# Sheet1.net
KiCad netlist of a schematic drawn in Altium Designer
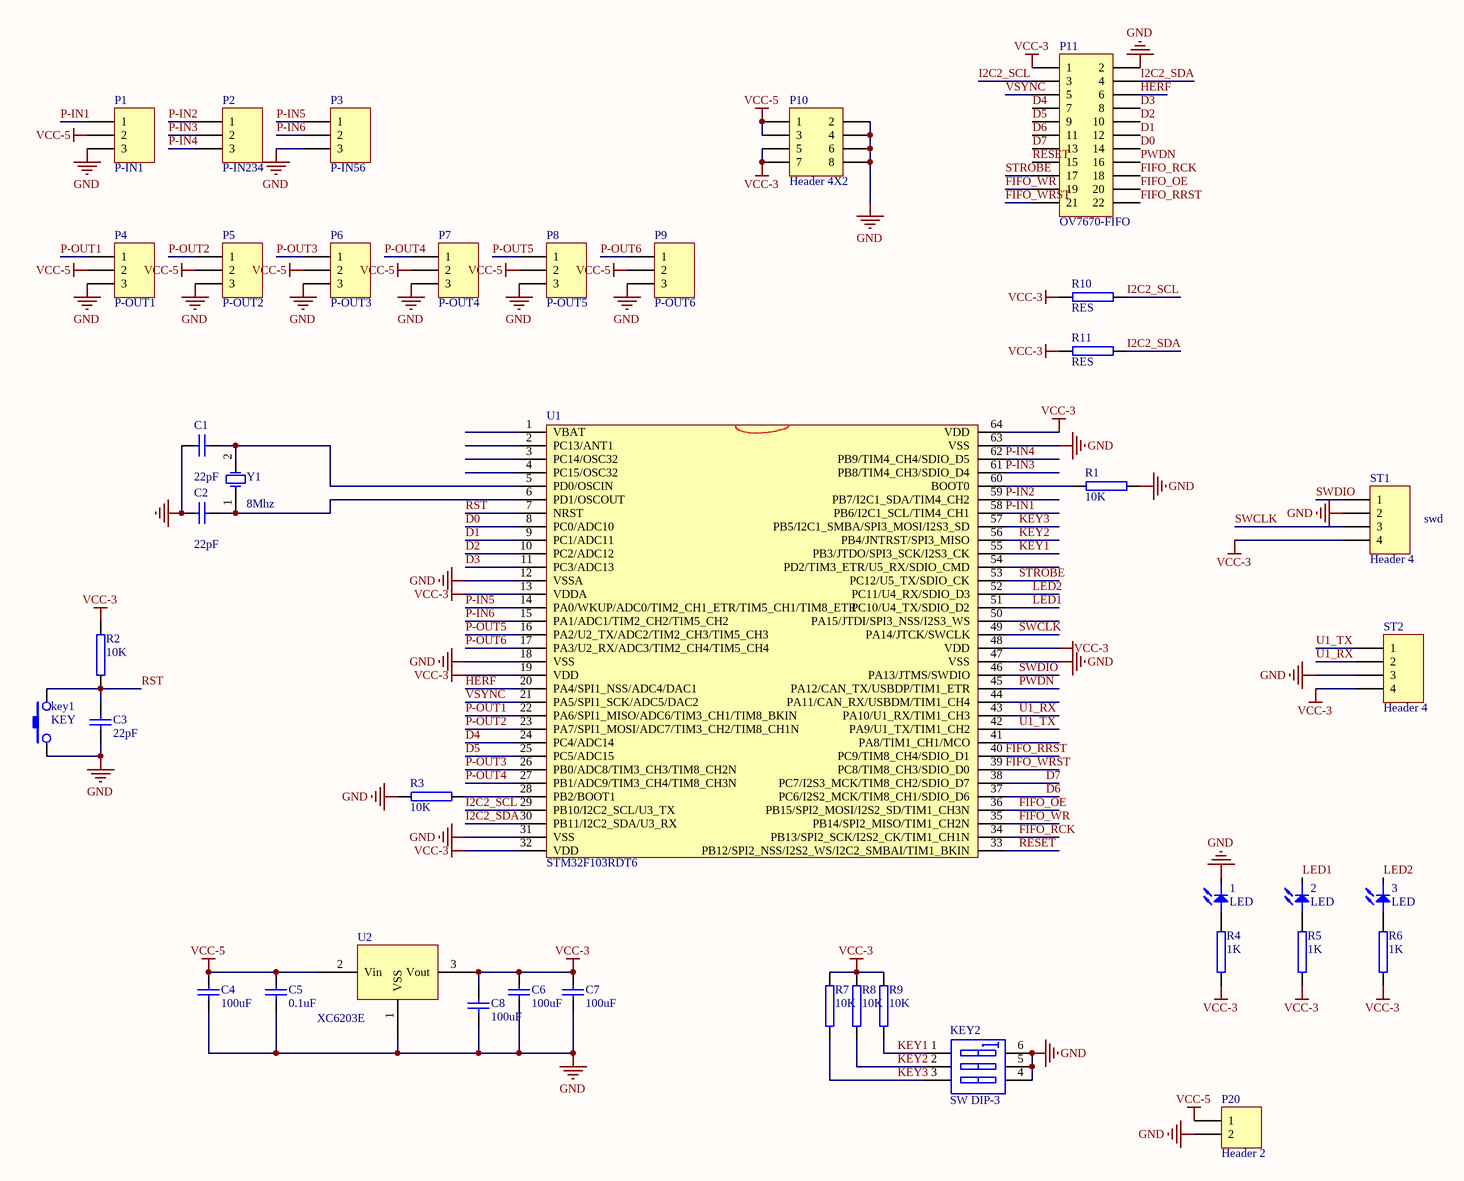
[diagram p0: Sheet1.SchDoc]

(export (version "E")
  (design (tool "Eeschema 10.0.6"))
  (components
    (comp (ref "1") (value "LED") (footprint "0603c") (libsource (lib "常用元件库") (part "LED")))
    (comp (ref "2") (value "LED") (footprint "0603c") (libsource (lib "常用元件库") (part "LED")))
    (comp (ref "3") (value "LED") (footprint "0603c") (libsource (lib "常用元件库") (part "LED")))
    (comp (ref "C1")
      (value "22pF")
      (footprint "0603c")
      (fields (field (name "Comment") "cap"))
      (libsource (lib "bai") (part "cap"))
    )
    (comp (ref "C2")
      (value "22pF")
      (footprint "0603c")
      (fields (field (name "Comment") "cap"))
      (libsource (lib "bai") (part "cap"))
    )
    (comp (ref "C3")
      (value "22pF")
      (footprint "0603c")
      (fields (field (name "Comment") "cap"))
      (libsource (lib "bai") (part "cap"))
    )
    (comp (ref "C4")
      (value "100uF")
      (footprint "0603c")
      (fields (field (name "Comment") "cap"))
      (libsource (lib "bai") (part "cap"))
    )
    (comp (ref "C5")
      (value "0.1uF")
      (footprint "0603c")
      (fields (field (name "Comment") "cap"))
      (libsource (lib "bai") (part "cap"))
    )
    (comp (ref "C6")
      (value "100uF")
      (footprint "0603c")
      (fields (field (name "Comment") "cap"))
      (libsource (lib "bai") (part "cap"))
    )
    (comp (ref "C7")
      (value "100uF")
      (footprint "0603c")
      (fields (field (name "Comment") "cap"))
      (libsource (lib "bai") (part "cap"))
    )
    (comp (ref "C8")
      (value "100uF")
      (footprint "0603c")
      (fields (field (name "Comment") "cap"))
      (libsource (lib "bai") (part "cap"))
    )
    (comp (ref "key1") (value "KEY") (footprint "7243") (libsource (lib "常用元件库") (part "KEY")))
    (comp (ref "KEY2")
      (value "SW DIP-3")
      (footprint "DIP6")
      (description "DIP Switch")
      (libsource (lib "开关") (part "SW DIP-3"))
    )
    (comp (ref "P1")
      (value "P-IN1")
      (footprint "HDR1X3")
      (description "Header, 3-Pin")
      (fields (field (name "PUBLISHER") "Altium Limited"))
      (libsource (lib "Miscellaneous Connectors") (part "MHDR1X3"))
    )
    (comp (ref "P2")
      (value "P-IN234")
      (footprint "HDR1X3")
      (description "Header, 3-Pin")
      (fields (field (name "PUBLISHER") "Altium Limited"))
      (libsource (lib "Miscellaneous Connectors") (part "MHDR1X3"))
    )
    (comp (ref "P3")
      (value "P-IN56")
      (footprint "HDR1X3")
      (description "Header, 3-Pin")
      (fields (field (name "PUBLISHER") "Altium Limited"))
      (libsource (lib "Miscellaneous Connectors") (part "MHDR1X3"))
    )
    (comp (ref "P4")
      (value "P-OUT1")
      (footprint "HDR1X3")
      (description "Header, 3-Pin")
      (fields (field (name "PUBLISHER") "Altium Limited"))
      (libsource (lib "Miscellaneous Connectors") (part "MHDR1X3"))
    )
    (comp (ref "P5")
      (value "P-OUT2")
      (footprint "HDR1X3")
      (description "Header, 3-Pin")
      (fields (field (name "PUBLISHER") "Altium Limited"))
      (libsource (lib "Miscellaneous Connectors") (part "MHDR1X3"))
    )
    (comp (ref "P6")
      (value "P-OUT3")
      (footprint "HDR1X3")
      (description "Header, 3-Pin")
      (fields (field (name "PUBLISHER") "Altium Limited"))
      (libsource (lib "Miscellaneous Connectors") (part "MHDR1X3"))
    )
    (comp (ref "P7")
      (value "P-OUT4")
      (footprint "HDR1X3")
      (description "Header, 3-Pin")
      (fields (field (name "PUBLISHER") "Altium Limited"))
      (libsource (lib "Miscellaneous Connectors") (part "MHDR1X3"))
    )
    (comp (ref "P8")
      (value "P-OUT5")
      (footprint "HDR1X3")
      (description "Header, 3-Pin")
      (fields (field (name "PUBLISHER") "Altium Limited"))
      (libsource (lib "Miscellaneous Connectors") (part "MHDR1X3"))
    )
    (comp (ref "P9")
      (value "P-OUT6")
      (footprint "HDR1X3")
      (description "Header, 3-Pin")
      (fields (field (name "PUBLISHER") "Altium Limited"))
      (libsource (lib "Miscellaneous Connectors") (part "MHDR1X3"))
    )
    (comp (ref "P10")
      (value "Header 4X2")
      (footprint "HDR2X4")
      (description "Header, 4-Pin, Dual row")
      (fields (field (name "PUBLISHER") "Altium Limited"))
      (libsource (lib "Miscellaneous Connectors") (part "Header 4X2"))
    )
    (comp (ref "P11")
      (value "OV7670-FIFO")
      (footprint "HDR2X11")
      (description "Header, 11-Pin, Dual row")
      (fields (field (name "PUBLISHER") "Altium Limited"))
      (libsource (lib "Miscellaneous Connectors") (part "Header 11X2"))
    )
    (comp (ref "P20")
      (value "Header 2")
      (footprint "HDR1X2")
      (description "Header, 2-Pin")
      (fields (field (name "PUBLISHER") "Altium Limited"))
      (libsource (lib "Miscellaneous Connectors") (part "Header 2"))
    )
    (comp (ref "R1") (value "10K") (footprint "0603c") (libsource (lib "常用元件库") (part "RES")))
    (comp (ref "R2") (value "10K") (footprint "0603c") (libsource (lib "常用元件库") (part "RES")))
    (comp (ref "R3") (value "10K") (footprint "0603c") (libsource (lib "常用元件库") (part "RES")))
    (comp (ref "R4") (value "1K") (footprint "0603c") (libsource (lib "常用元件库") (part "RES")))
    (comp (ref "R5") (value "1K") (footprint "0603c") (libsource (lib "常用元件库") (part "RES")))
    (comp (ref "R6") (value "1K") (footprint "0603c") (libsource (lib "常用元件库") (part "RES")))
    (comp (ref "R7") (value "10K") (footprint "0603c") (libsource (lib "常用元件库") (part "RES")))
    (comp (ref "R8") (value "10K") (footprint "0603c") (libsource (lib "常用元件库") (part "RES")))
    (comp (ref "R9") (value "10K") (footprint "0603c") (libsource (lib "常用元件库") (part "RES")))
    (comp (ref "R10") (value "RES") (footprint "0603c") (libsource (lib "常用元件库") (part "RES")))
    (comp (ref "R11") (value "RES") (footprint "0603c") (libsource (lib "常用元件库") (part "RES")))
    (comp (ref "ST1")
      (value "Header 4")
      (footprint "HDR1X4")
      (description "Header, 4-Pin")
      (fields (field (name "PUBLISHER") "Altium Limited"))
      (libsource (lib "Miscellaneous Connectors") (part "Header 4"))
    )
    (comp (ref "ST2")
      (value "Header 4")
      (footprint "HDR1X4")
      (description "Header, 4-Pin")
      (fields (field (name "PUBLISHER") "Altium Limited"))
      (libsource (lib "Miscellaneous Connectors") (part "Header 4"))
    )
    (comp (ref "U1")
      (value "STM32F103RDT6")
      (footprint "stm32:LQFP64")
      (libsource (lib "stm32") (part "STM32F103RDT6"))
    )
    (comp (ref "U2") (value "XC6203E") (footprint "SOT-89") (libsource (lib "文哥做的") (part "XC6203")))
    (comp (ref "Y1")
      (value "5032xtal")
      (footprint "XTAL")
      (fields (field (name "ALTIUM_UNNAMED_1") "8Mhz"))
      (libsource (lib "bai") (part "5032xtal"))
    )
  )
  (nets
    (net (code "1") (name "/D0") (class "Default")
      (node (ref "P11") (pin "14") (pinfunction "14_14") (pintype "passive"))
      (node (ref "U1") (pin "8") (pinfunction "PC0/ADC10_8") (pintype "passive"))
    )
    (net (code "2") (name "/D1") (class "Default")
      (node (ref "P11") (pin "12") (pinfunction "12_12") (pintype "passive"))
      (node (ref "U1") (pin "9") (pinfunction "PC1/ADC11_9") (pintype "passive"))
    )
    (net (code "3") (name "/D2") (class "Default")
      (node (ref "P11") (pin "10") (pinfunction "10_10") (pintype "passive"))
      (node (ref "U1") (pin "10") (pinfunction "PC2/ADC12_10") (pintype "passive"))
    )
    (net (code "4") (name "/D3") (class "Default")
      (node (ref "P11") (pin "8") (pinfunction "8_8") (pintype "passive"))
      (node (ref "U1") (pin "11") (pinfunction "PC3/ADC13_11") (pintype "passive"))
    )
    (net (code "5") (name "/D4") (class "Default")
      (node (ref "P11") (pin "7") (pinfunction "7_7") (pintype "passive"))
      (node (ref "U1") (pin "24") (pinfunction "PC4/ADC14_24") (pintype "passive"))
    )
    (net (code "6") (name "/D5") (class "Default")
      (node (ref "P11") (pin "9") (pinfunction "9_9") (pintype "passive"))
      (node (ref "U1") (pin "25") (pinfunction "PC5/ADC15_25") (pintype "passive"))
    )
    (net (code "7") (name "/D6") (class "Default")
      (node (ref "P11") (pin "11") (pinfunction "11_11") (pintype "passive"))
      (node (ref "U1") (pin "37") (pinfunction "PC6/I2S2_MCK/TIM8_CH1/SDIO_D6_37") (pintype "passive"))
    )
    (net (code "8") (name "/D7") (class "Default")
      (node (ref "P11") (pin "13") (pinfunction "13_13") (pintype "passive"))
      (node (ref "U1") (pin "38") (pinfunction "PC7/I2S3_MCK/TIM8_CH2/SDIO_D7_38") (pintype "passive"))
    )
    (net (code "9") (name "/FIFO_OE") (class "Default")
      (node (ref "P11") (pin "20") (pinfunction "20_20") (pintype "passive"))
      (node (ref "U1") (pin "36") (pinfunction "PB15/SPI2_MOSI/I2S2_SD/TIM1_CH3N_36") (pintype "passive"))
    )
    (net (code "10") (name "/FIFO_RCK") (class "Default")
      (node (ref "P11") (pin "18") (pinfunction "18_18") (pintype "passive"))
      (node (ref "U1") (pin "34") (pinfunction "PB13/SPI2_SCK/I2S2_CK/TIM1_CH1N_34") (pintype "passive"))
    )
    (net (code "11") (name "/FIFO_RRST") (class "Default")
      (node (ref "P11") (pin "22") (pinfunction "22_22") (pintype "passive"))
      (node (ref "U1") (pin "40") (pinfunction "PC9/TIM8_CH4/SDIO_D1_40") (pintype "passive"))
    )
    (net (code "12") (name "/FIFO_WR") (class "Default")
      (node (ref "P11") (pin "19") (pinfunction "19_19") (pintype "passive"))
      (node (ref "U1") (pin "35") (pinfunction "PB14/SPI2_MISO/TIM1_CH2N_35") (pintype "passive"))
    )
    (net (code "13") (name "/FIFO_WRST") (class "Default")
      (node (ref "P11") (pin "21") (pinfunction "21_21") (pintype "passive"))
      (node (ref "U1") (pin "39") (pinfunction "PC8/TIM8_CH3/SDIO_D0_39") (pintype "passive"))
    )
    (net (code "14") (name "/HERF") (class "Default")
      (node (ref "P11") (pin "6") (pinfunction "6_6") (pintype "passive"))
      (node (ref "U1") (pin "20") (pinfunction "PA4/SPI1_NSS/ADC4/DAC1_20") (pintype "passive"))
    )
    (net (code "15") (name "/I2C2_SCL") (class "Default")
      (node (ref "P11") (pin "3") (pinfunction "3_3") (pintype "passive"))
      (node (ref "R10") (pin "2") (pinfunction "2_2") (pintype "passive"))
      (node (ref "U1") (pin "29") (pinfunction "PB10/I2C2_SCL/U3_TX_29") (pintype "passive"))
    )
    (net (code "16") (name "/I2C2_SDA") (class "Default")
      (node (ref "P11") (pin "4") (pinfunction "4_4") (pintype "passive"))
      (node (ref "R11") (pin "2") (pinfunction "2_2") (pintype "passive"))
      (node (ref "U1") (pin "30") (pinfunction "PB11/I2C2_SDA/U3_RX_30") (pintype "passive"))
    )
    (net (code "17") (name "/KEY1") (class "Default")
      (node (ref "KEY2") (pin "1") (pinfunction "A1_1") (pintype "passive"))
      (node (ref "R9") (pin "1") (pinfunction "1_1") (pintype "passive"))
      (node (ref "U1") (pin "55") (pinfunction "PB3/JTDO/SPI3_SCK/I2S3_CK_55") (pintype "passive"))
    )
    (net (code "18") (name "/KEY2") (class "Default")
      (node (ref "KEY2") (pin "2") (pinfunction "A2_2") (pintype "passive"))
      (node (ref "R8") (pin "1") (pinfunction "1_1") (pintype "passive"))
      (node (ref "U1") (pin "56") (pinfunction "PB4/JNTRST/SPI3_MISO_56") (pintype "passive"))
    )
    (net (code "19") (name "/KEY3") (class "Default")
      (node (ref "KEY2") (pin "3") (pinfunction "A3_3") (pintype "passive"))
      (node (ref "R7") (pin "1") (pinfunction "1_1") (pintype "passive"))
      (node (ref "U1") (pin "57") (pinfunction "PB5/I2C1_SMBA/SPI3_MOSI/I2S3_SD_57") (pintype "passive"))
    )
    (net (code "20") (name "/LED1") (class "Default")
      (node (ref "2") (pin "K") (pintype "passive"))
      (node (ref "U1") (pin "51") (pinfunction "PC10/U4_TX/SDIO_D2_51") (pintype "passive"))
    )
    (net (code "21") (name "/LED2") (class "Default")
      (node (ref "3") (pin "K") (pintype "passive"))
      (node (ref "U1") (pin "52") (pinfunction "PC11/U4_RX/SDIO_D3_52") (pintype "passive"))
    )
    (net (code "22") (name "/P-IN1") (class "Default")
      (node (ref "P1") (pin "1") (pinfunction "1_1") (pintype "passive"))
      (node (ref "U1") (pin "58") (pinfunction "PB6/I2C1_SCL/TIM4_CH1_58") (pintype "passive"))
    )
    (net (code "23") (name "/P-IN2") (class "Default")
      (node (ref "P2") (pin "1") (pinfunction "1_1") (pintype "passive"))
      (node (ref "U1") (pin "59") (pinfunction "PB7/I2C1_SDA/TIM4_CH2_59") (pintype "passive"))
    )
    (net (code "24") (name "/P-IN3") (class "Default")
      (node (ref "P2") (pin "2") (pinfunction "2_2") (pintype "passive"))
      (node (ref "U1") (pin "61") (pinfunction "PB8/TIM4_CH3/SDIO_D4_61") (pintype "passive"))
    )
    (net (code "25") (name "/P-IN4") (class "Default")
      (node (ref "P2") (pin "3") (pinfunction "3_3") (pintype "passive"))
      (node (ref "U1") (pin "62") (pinfunction "PB9/TIM4_CH4/SDIO_D5_62") (pintype "passive"))
    )
    (net (code "26") (name "/P-IN5") (class "Default")
      (node (ref "P3") (pin "1") (pinfunction "1_1") (pintype "passive"))
      (node (ref "U1") (pin "14") (pinfunction "PA0/WKUP/ADC0/TIM2_CH1_ETR/TIM5_CH1/TIM8_ETR_14") (pintype "passive"))
    )
    (net (code "27") (name "/P-IN6") (class "Default")
      (node (ref "P3") (pin "2") (pinfunction "2_2") (pintype "passive"))
      (node (ref "U1") (pin "15") (pinfunction "PA1/ADC1/TIM2_CH2/TIM5_CH2_15") (pintype "passive"))
    )
    (net (code "28") (name "/P-OUT1") (class "Default")
      (node (ref "P4") (pin "1") (pinfunction "1_1") (pintype "passive"))
      (node (ref "U1") (pin "22") (pinfunction "PA6/SPI1_MISO/ADC6/TIM3_CH1/TIM8_BKIN_22") (pintype "passive"))
    )
    (net (code "29") (name "/P-OUT2") (class "Default")
      (node (ref "P5") (pin "1") (pinfunction "1_1") (pintype "passive"))
      (node (ref "U1") (pin "23") (pinfunction "PA7/SPI1_MOSI/ADC7/TIM3_CH2/TIM8_CH1N_23") (pintype "passive"))
    )
    (net (code "30") (name "/P-OUT3") (class "Default")
      (node (ref "P6") (pin "1") (pinfunction "1_1") (pintype "passive"))
      (node (ref "U1") (pin "26") (pinfunction "PB0/ADC8/TIM3_CH3/TIM8_CH2N_26") (pintype "passive"))
    )
    (net (code "31") (name "/P-OUT4") (class "Default")
      (node (ref "P7") (pin "1") (pinfunction "1_1") (pintype "passive"))
      (node (ref "U1") (pin "27") (pinfunction "PB1/ADC9/TIM3_CH4/TIM8_CH3N_27") (pintype "passive"))
    )
    (net (code "32") (name "/P-OUT5") (class "Default")
      (node (ref "P8") (pin "1") (pinfunction "1_1") (pintype "passive"))
      (node (ref "U1") (pin "16") (pinfunction "PA2/U2_TX/ADC2/TIM2_CH3/TIM5_CH3_16") (pintype "passive"))
    )
    (net (code "33") (name "/P-OUT6") (class "Default")
      (node (ref "P9") (pin "1") (pinfunction "1_1") (pintype "passive"))
      (node (ref "U1") (pin "17") (pinfunction "PA3/U2_RX/ADC3/TIM2_CH4/TIM5_CH4_17") (pintype "passive"))
    )
    (net (code "34") (name "/PWDN") (class "Default")
      (node (ref "P11") (pin "16") (pinfunction "16_16") (pintype "passive"))
      (node (ref "U1") (pin "45") (pinfunction "PA12/CAN_TX/USBDP/TIM1_ETR_45") (pintype "passive"))
    )
    (net (code "35") (name "/RESET") (class "Default")
      (node (ref "P11") (pin "15") (pinfunction "15_15") (pintype "passive"))
      (node (ref "U1") (pin "33") (pinfunction "PB12/SPI2_NSS/I2S2_WS/I2C2_SMBAI/TIM1_BKIN_33") (pintype "passive"))
    )
    (net (code "36") (name "/RST") (class "Default")
      (node (ref "C3") (pin "2") (pinfunction "2_2") (pintype "passive"))
      (node (ref "R2") (pin "1") (pinfunction "1_1") (pintype "passive"))
      (node (ref "U1") (pin "7") (pinfunction "NRST_7") (pintype "passive"))
      (node (ref "key1") (pin "2") (pinfunction "2_2") (pintype "passive"))
    )
    (net (code "37") (name "/STROBE") (class "Default")
      (node (ref "P11") (pin "17") (pinfunction "17_17") (pintype "passive"))
      (node (ref "U1") (pin "53") (pinfunction "PC12/U5_TX/SDIO_CK_53") (pintype "passive"))
    )
    (net (code "38") (name "/SWCLK") (class "Default")
      (node (ref "ST1") (pin "3") (pinfunction "3_3") (pintype "passive"))
      (node (ref "U1") (pin "49") (pinfunction "PA14/JTCK/SWCLK_49") (pintype "passive"))
    )
    (net (code "39") (name "/SWDIO") (class "Default")
      (node (ref "ST1") (pin "1") (pinfunction "1_1") (pintype "passive"))
      (node (ref "U1") (pin "46") (pinfunction "PA13/JTMS/SWDIO_46") (pintype "passive"))
    )
    (net (code "40") (name "/U1_RX") (class "Default")
      (node (ref "ST2") (pin "2") (pinfunction "2_2") (pintype "passive"))
      (node (ref "U1") (pin "43") (pinfunction "PA10/U1_RX/TIM1_CH3_43") (pintype "passive"))
    )
    (net (code "41") (name "/U1_TX") (class "Default")
      (node (ref "ST2") (pin "1") (pinfunction "1_1") (pintype "passive"))
      (node (ref "U1") (pin "42") (pinfunction "PA9/U1_TX/TIM1_CH2_42") (pintype "passive"))
    )
    (net (code "42") (name "/VSYNC") (class "Default")
      (node (ref "P11") (pin "5") (pinfunction "5_5") (pintype "passive"))
      (node (ref "U1") (pin "21") (pinfunction "PA5/SPI1_SCK/ADC5/DAC2_21") (pintype "passive"))
    )
    (net (code "43") (name "GND") (class "Default")
      (node (ref "1") (pin "K") (pintype "passive"))
      (node (ref "C1") (pin "1") (pinfunction "1_1") (pintype "passive"))
      (node (ref "C2") (pin "1") (pinfunction "1_1") (pintype "passive"))
      (node (ref "C3") (pin "1") (pinfunction "1_1") (pintype "passive"))
      (node (ref "C4") (pin "1") (pinfunction "1_1") (pintype "passive"))
      (node (ref "C5") (pin "1") (pinfunction "1_1") (pintype "passive"))
      (node (ref "C6") (pin "1") (pinfunction "1_1") (pintype "passive"))
      (node (ref "C7") (pin "1") (pinfunction "1_1") (pintype "passive"))
      (node (ref "C8") (pin "1") (pinfunction "1_1") (pintype "passive"))
      (node (ref "KEY2") (pin "4") (pinfunction "B3_4") (pintype "passive"))
      (node (ref "KEY2") (pin "5") (pinfunction "B2_5") (pintype "passive"))
      (node (ref "KEY2") (pin "6") (pinfunction "B1_6") (pintype "passive"))
      (node (ref "P1") (pin "3") (pinfunction "3_3") (pintype "passive"))
      (node (ref "P10") (pin "2") (pinfunction "2_2") (pintype "passive"))
      (node (ref "P10") (pin "4") (pinfunction "4_4") (pintype "passive"))
      (node (ref "P10") (pin "6") (pinfunction "6_6") (pintype "passive"))
      (node (ref "P10") (pin "8") (pinfunction "8_8") (pintype "passive"))
      (node (ref "P11") (pin "2") (pinfunction "2_2") (pintype "passive"))
      (node (ref "P20") (pin "2") (pinfunction "2_2") (pintype "passive"))
      (node (ref "P3") (pin "3") (pinfunction "3_3") (pintype "passive"))
      (node (ref "P4") (pin "3") (pinfunction "3_3") (pintype "passive"))
      (node (ref "P5") (pin "3") (pinfunction "3_3") (pintype "passive"))
      (node (ref "P6") (pin "3") (pinfunction "3_3") (pintype "passive"))
      (node (ref "P7") (pin "3") (pinfunction "3_3") (pintype "passive"))
      (node (ref "P8") (pin "3") (pinfunction "3_3") (pintype "passive"))
      (node (ref "P9") (pin "3") (pinfunction "3_3") (pintype "passive"))
      (node (ref "R1") (pin "2") (pinfunction "2_2") (pintype "passive"))
      (node (ref "R3") (pin "2") (pinfunction "2_2") (pintype "passive"))
      (node (ref "ST1") (pin "2") (pinfunction "2_2") (pintype "passive"))
      (node (ref "ST2") (pin "3") (pinfunction "3_3") (pintype "passive"))
      (node (ref "U1") (pin "12") (pinfunction "VSSA_12") (pintype "passive"))
      (node (ref "U1") (pin "18") (pinfunction "VSS_18") (pintype "passive"))
      (node (ref "U1") (pin "31") (pinfunction "VSS_31") (pintype "passive"))
      (node (ref "U1") (pin "47") (pinfunction "VSS_47") (pintype "passive"))
      (node (ref "U1") (pin "63") (pinfunction "VSS_63") (pintype "passive"))
      (node (ref "U2") (pin "1") (pinfunction "VSS_1") (pintype "passive"))
      (node (ref "key1") (pin "1") (pinfunction "1_1") (pintype "passive"))
    )
    (net (code "44") (name "Net-(1-PadA)") (class "Default")
      (node (ref "1") (pin "A") (pintype "passive"))
      (node (ref "R4") (pin "2") (pinfunction "2_2") (pintype "passive"))
    )
    (net (code "45") (name "Net-(2-PadA)") (class "Default")
      (node (ref "2") (pin "A") (pintype "passive"))
      (node (ref "R5") (pin "2") (pinfunction "2_2") (pintype "passive"))
    )
    (net (code "46") (name "Net-(3-PadA)") (class "Default")
      (node (ref "3") (pin "A") (pintype "passive"))
      (node (ref "R6") (pin "2") (pinfunction "2_2") (pintype "passive"))
    )
    (net (code "47") (name "Net-(U1-BOOT0)") (class "Default")
      (node (ref "R1") (pin "1") (pinfunction "1_1") (pintype "passive"))
      (node (ref "U1") (pin "60") (pinfunction "BOOT0_60") (pintype "passive"))
    )
    (net (code "48") (name "Net-(U1-PB2{slash}BOOT1)") (class "Default")
      (node (ref "R3") (pin "1") (pinfunction "1_1") (pintype "passive"))
      (node (ref "U1") (pin "28") (pinfunction "PB2/BOOT1_28") (pintype "passive"))
    )
    (net (code "49") (name "Net-(U1-PD0{slash}OSCIN)") (class "Default")
      (node (ref "C1") (pin "2") (pinfunction "2_2") (pintype "passive"))
      (node (ref "U1") (pin "5") (pinfunction "PD0/OSCIN_5") (pintype "passive"))
      (node (ref "Y1") (pin "2") (pinfunction "OSC2_2") (pintype "passive"))
    )
    (net (code "50") (name "Net-(U1-PD1{slash}OSCOUT)") (class "Default")
      (node (ref "C2") (pin "2") (pinfunction "2_2") (pintype "passive"))
      (node (ref "U1") (pin "6") (pinfunction "PD1/OSCOUT_6") (pintype "passive"))
      (node (ref "Y1") (pin "1") (pinfunction "OSC1_1") (pintype "passive"))
    )
    (net (code "51") (name "VCC-3") (class "Default")
      (node (ref "C6") (pin "2") (pinfunction "2_2") (pintype "passive"))
      (node (ref "C7") (pin "2") (pinfunction "2_2") (pintype "passive"))
      (node (ref "C8") (pin "2") (pinfunction "2_2") (pintype "passive"))
      (node (ref "P10") (pin "5") (pinfunction "5_5") (pintype "passive"))
      (node (ref "P10") (pin "7") (pinfunction "7_7") (pintype "passive"))
      (node (ref "P11") (pin "1") (pinfunction "1_1") (pintype "passive"))
      (node (ref "R10") (pin "1") (pinfunction "1_1") (pintype "passive"))
      (node (ref "R11") (pin "1") (pinfunction "1_1") (pintype "passive"))
      (node (ref "R2") (pin "2") (pinfunction "2_2") (pintype "passive"))
      (node (ref "R4") (pin "1") (pinfunction "1_1") (pintype "passive"))
      (node (ref "R5") (pin "1") (pinfunction "1_1") (pintype "passive"))
      (node (ref "R6") (pin "1") (pinfunction "1_1") (pintype "passive"))
      (node (ref "R7") (pin "2") (pinfunction "2_2") (pintype "passive"))
      (node (ref "R8") (pin "2") (pinfunction "2_2") (pintype "passive"))
      (node (ref "R9") (pin "2") (pinfunction "2_2") (pintype "passive"))
      (node (ref "ST1") (pin "4") (pinfunction "4_4") (pintype "passive"))
      (node (ref "ST2") (pin "4") (pinfunction "4_4") (pintype "passive"))
      (node (ref "U1") (pin "13") (pinfunction "VDDA_13") (pintype "passive"))
      (node (ref "U1") (pin "19") (pinfunction "VDD_19") (pintype "passive"))
      (node (ref "U1") (pin "32") (pinfunction "VDD_32") (pintype "passive"))
      (node (ref "U1") (pin "48") (pinfunction "VDD_48") (pintype "passive"))
      (node (ref "U1") (pin "64") (pinfunction "VDD_64") (pintype "passive"))
      (node (ref "U2") (pin "3") (pinfunction "Vout_3") (pintype "passive"))
    )
    (net (code "52") (name "VCC-5") (class "Default")
      (node (ref "C4") (pin "2") (pinfunction "2_2") (pintype "passive"))
      (node (ref "C5") (pin "2") (pinfunction "2_2") (pintype "passive"))
      (node (ref "P1") (pin "2") (pinfunction "2_2") (pintype "passive"))
      (node (ref "P10") (pin "1") (pinfunction "1_1") (pintype "passive"))
      (node (ref "P10") (pin "3") (pinfunction "3_3") (pintype "passive"))
      (node (ref "P20") (pin "1") (pinfunction "1_1") (pintype "passive"))
      (node (ref "P4") (pin "2") (pinfunction "2_2") (pintype "passive"))
      (node (ref "P5") (pin "2") (pinfunction "2_2") (pintype "passive"))
      (node (ref "P6") (pin "2") (pinfunction "2_2") (pintype "passive"))
      (node (ref "P7") (pin "2") (pinfunction "2_2") (pintype "passive"))
      (node (ref "P8") (pin "2") (pinfunction "2_2") (pintype "passive"))
      (node (ref "P9") (pin "2") (pinfunction "2_2") (pintype "passive"))
      (node (ref "U2") (pin "2") (pinfunction "Vin_2") (pintype "passive"))
    )
    (net (code "53") (name "unconnected-(U1-PA8{slash}TIM1_CH1{slash}MCO-Pad41)") (class "Default")
      (node (ref "U1") (pin "41") (pinfunction "PA8/TIM1_CH1/MCO_41") (pintype "passive"))
    )
    (net (code "54") (name "unconnected-(U1-PA11{slash}CAN_RX{slash}USBDM{slash}TIM1_CH4-Pad44)") (class "Default")
      (node (ref "U1") (pin "44") (pinfunction "PA11/CAN_RX/USBDM/TIM1_CH4_44") (pintype "passive"))
    )
    (net (code "55") (name "unconnected-(U1-PA15{slash}JTDI{slash}SPI3_NSS{slash}I2S3_WS-Pad50)") (class "Default")
      (node (ref "U1") (pin "50") (pinfunction "PA15/JTDI/SPI3_NSS/I2S3_WS_50") (pintype "passive"))
    )
    (net (code "56") (name "unconnected-(U1-PC13{slash}ANT1-Pad2)") (class "Default")
      (node (ref "U1") (pin "2") (pinfunction "PC13/ANT1_2") (pintype "passive"))
    )
    (net (code "57") (name "unconnected-(U1-PC14{slash}OSC32-Pad3)") (class "Default")
      (node (ref "U1") (pin "3") (pinfunction "PC14/OSC32_3") (pintype "passive"))
    )
    (net (code "58") (name "unconnected-(U1-PC15{slash}OSC32-Pad4)") (class "Default")
      (node (ref "U1") (pin "4") (pinfunction "PC15/OSC32_4") (pintype "passive"))
    )
    (net (code "59") (name "unconnected-(U1-PD2{slash}TIM3_ETR{slash}U5_RX{slash}SDIO_CMD-Pad54)") (class "Default")
      (node (ref "U1") (pin "54") (pinfunction "PD2/TIM3_ETR/U5_RX/SDIO_CMD_54") (pintype "passive"))
    )
    (net (code "60") (name "unconnected-(U1-VBAT-Pad1)") (class "Default")
      (node (ref "U1") (pin "1") (pinfunction "VBAT_1") (pintype "passive"))
    )
  )
)
